# Power_subsystem.net
KiCad netlist of a schematic drawn in Altium Designer
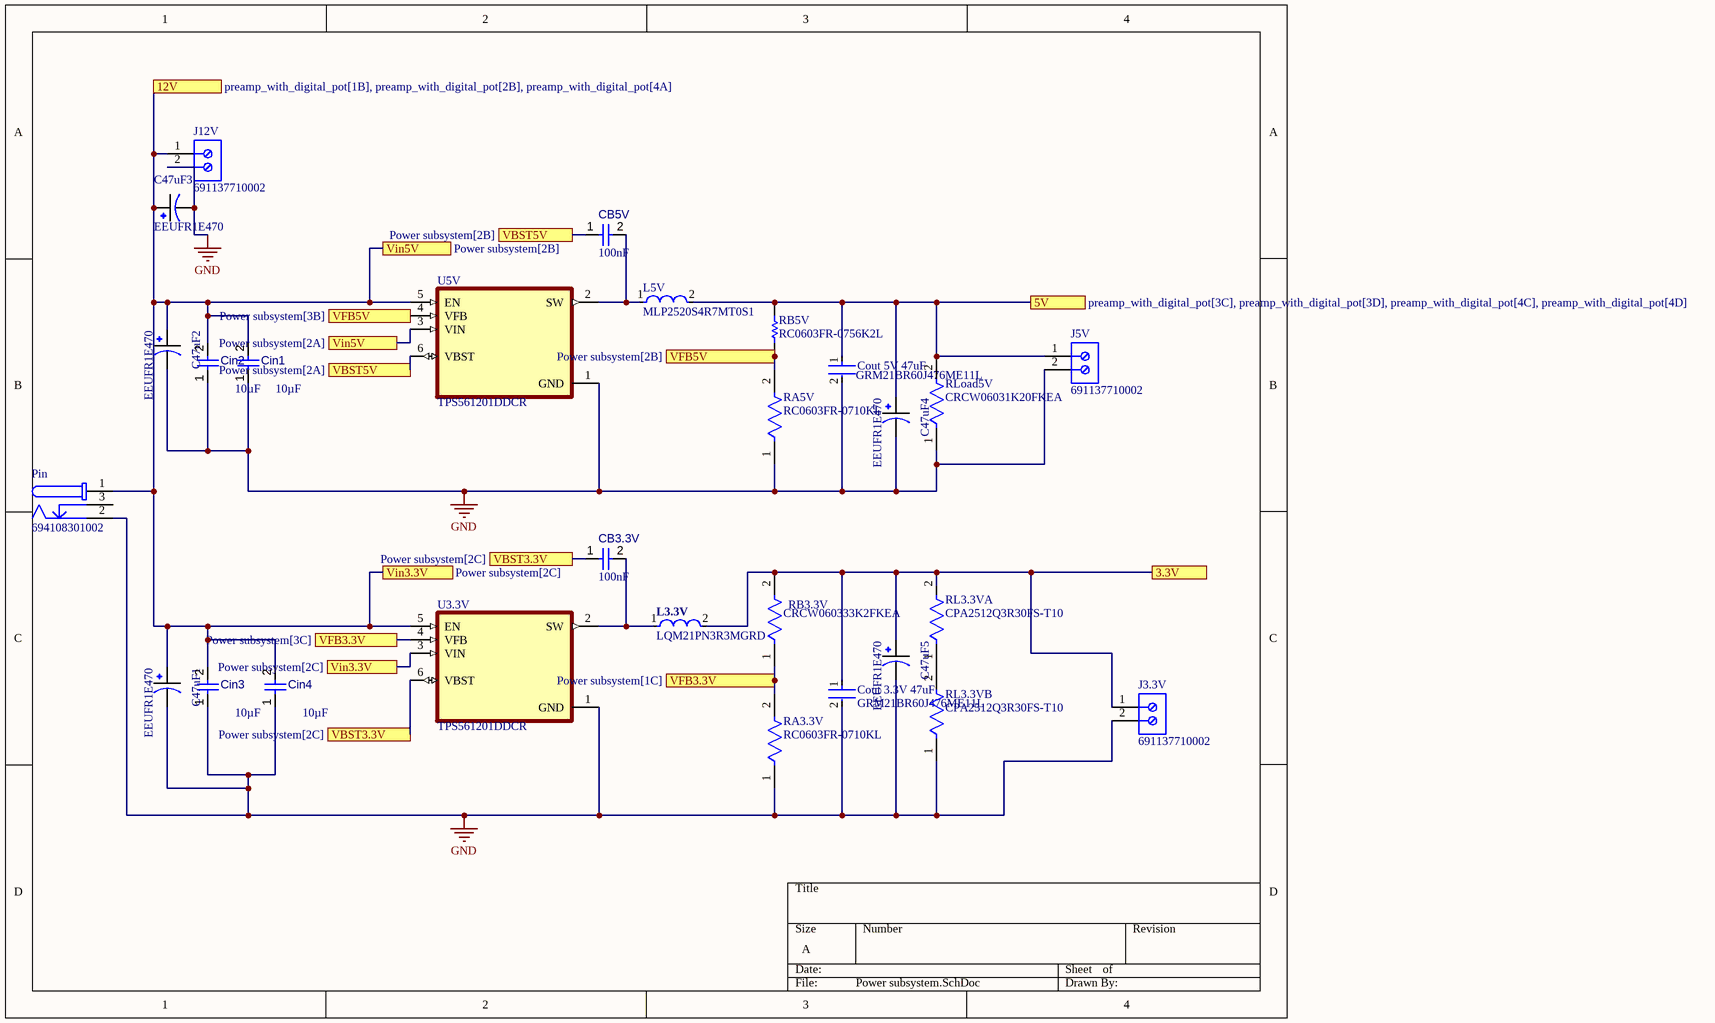
[diagram p0: Power subsystem.SchDoc]

(export (version "E")
  (design (tool "Eeschema 10.0.6"))
  (components
    (comp (ref "C47uF1")
      (value "EEUFR1E470")
      (footprint "*CAPPRD200W50D500H1100_EEUFR1E470(Primary)")
      (libsource (lib "EEUFR1E470") (part "EEUFR1E470"))
    )
    (comp (ref "C47uF2")
      (value "EEUFR1E470")
      (footprint "*CAPPRD200W50D500H1100_EEUFR1E470(Primary)")
      (libsource (lib "EEUFR1E470") (part "EEUFR1E470"))
    )
    (comp (ref "C47uF3")
      (value "EEUFR1E470")
      (footprint "*CAPPRD200W50D500H1100_EEUFR1E470(Primary)")
      (libsource (lib "EEUFR1E470") (part "EEUFR1E470"))
    )
    (comp (ref "C47uF4")
      (value "EEUFR1E470")
      (footprint "*CAPPRD200W50D500H1100_EEUFR1E470(Primary)")
      (libsource (lib "EEUFR1E470") (part "EEUFR1E470"))
    )
    (comp (ref "C47uF5")
      (value "EEUFR1E470")
      (footprint "*CAPPRD200W50D500H1100_EEUFR1E470(Primary)")
      (libsource (lib "EEUFR1E470") (part "EEUFR1E470"))
    )
    (comp (ref "CB3.3V")
      (value "100nF")
      (footprint "CAPC1608X90X40NL10T20")
      (description "Chip Capacitor, 100 nF, +/- 10%, 50 V, 0603 (1608 Metric)")
      (fields (field (name "TOLERANCE") "10%") (field (name "Comment") "Capacitor 100 nF +/-10% 50 V 0603"))
      (libsource (lib "Braeden Murdock") (part "CAP-NP-2"))
    )
    (comp (ref "CB5V")
      (value "100nF")
      (footprint "CAPC1608X90X40NL10T20")
      (description "Chip Capacitor, 100 nF, +/- 10%, 50 V, 0603 (1608 Metric)")
      (fields (field (name "TOLERANCE") "10%") (field (name "Comment") "Capacitor 100 nF +/-10% 50 V 0603"))
      (libsource (lib "Braeden Murdock") (part "CAP-NP-2"))
    )
    (comp (ref "Cin1")
      (value "10µF")
      (footprint "CAPC0805(2012)145_L")
      (description "Chip Capacitor, 10µF +/-20%, 25V, 0805, Thickness 1.45 mm")
      (fields (field (name "TOLERANCE") "10%") (field (name "Comment") "Capacitor 10µF +/-20% 25V 0805"))
      (libsource (lib "Braeden Murdock") (part "CAP-NP-2"))
    )
    (comp (ref "Cin2")
      (value "10µF")
      (footprint "CAPC0805(2012)145_L")
      (description "Chip Capacitor, 10µF +/-20%, 25V, 0805, Thickness 1.45 mm")
      (fields (field (name "TOLERANCE") "10%") (field (name "Comment") "Capacitor 10µF +/-20% 25V 0805"))
      (libsource (lib "Braeden Murdock") (part "CAP-NP-2"))
    )
    (comp (ref "Cin3")
      (value "10µF")
      (footprint "CAPC0805(2012)145_L")
      (description "Chip Capacitor, 10µF +/-20%, 25V, 0805, Thickness 1.45 mm")
      (fields (field (name "TOLERANCE") "10%") (field (name "Comment") "Capacitor 10µF +/-20% 25V 0805"))
      (libsource (lib "Braeden Murdock") (part "CAP-NP-2"))
    )
    (comp (ref "Cin4")
      (value "10µF")
      (footprint "CAPC0805(2012)145_L")
      (description "Chip Capacitor, 10µF +/-20%, 25V, 0805, Thickness 1.45 mm")
      (fields (field (name "TOLERANCE") "10%") (field (name "Comment") "Capacitor 10µF +/-20% 25V 0805"))
      (libsource (lib "Braeden Murdock") (part "CAP-NP-2"))
    )
    (comp (ref "Cout 3.3V 47uF")
      (value "GRM21BR60J476ME11L")
      (footprint "FP-GRM21B-0_2-e0_2_0_7-IPC_B")
      (description "Chip Multilayer Ceramic Capacitors for General Purpose, 0805, 47uF, X5R, 15%, 20%, 6.3V")
      (fields (field (name "TOLERANCE") "20%"))
      (libsource (lib "Altium Content Vault") (part "b4654b650e69147ec39a6b967a45e02"))
    )
    (comp (ref "Cout 5V 47uF")
      (value "GRM21BR60J476ME11L")
      (footprint "FP-GRM21B-0_2-e0_2_0_7-IPC_B")
      (description "Chip Multilayer Ceramic Capacitors for General Purpose, 0805, 47uF, X5R, 15%, 20%, 6.3V")
      (fields (field (name "TOLERANCE") "20%"))
      (libsource (lib "Altium Content Vault") (part "b4654b650e69147ec39a6b967a45e02"))
    )
    (comp (ref "J3.3V")
      (value "691137710002")
      (footprint "691137710002")
      (libsource (lib "Altium Content Vault") (part "TBL - 1R - 02P - Screw"))
    )
    (comp (ref "J5V")
      (value "691137710002")
      (footprint "691137710002")
      (libsource (lib "Altium Content Vault") (part "TBL - 1R - 02P - Screw"))
    )
    (comp (ref "J12V")
      (value "691137710002")
      (footprint "691137710002")
      (libsource (lib "Altium Content Vault") (part "TBL - 1R - 02P - Screw"))
    )
    (comp (ref "L3.3V")
      (value "LQM21PN3R3MGRD")
      (footprint "FP-LQM21PH_G0-MFG")
      (description "Multilayer Type Inductor for Power Lines, 0805 (2012), 3.3μH, 20%, 0.188Ω, 1.0A")
      (fields (field (name "TOLERANCE") "20%"))
      (libsource (lib "Altium Content Vault") (part "725321dda6339637d4d059423bc1c3c"))
    )
    (comp (ref "L5V")
      (value "MLP2520S4R7MT0S1")
      (footprint "FP-MLP2520M-IPC_C")
      (description "Shielded Multilayer Inductor 4.7uH ±20% 1000mA 169mΩ SMD 1008")
      (fields (field (name "TOLERANCE") "20%"))
      (libsource (lib "Altium Content Vault") (part "725321dda6339637d4d059423bc1c3c"))
    )
    (comp (ref "Pin")
      (value "694108301002")
      (footprint "694108301002")
      (libsource (lib "Altium Content Vault") (part "DC Power Jack"))
    )
    (comp (ref "RA3.3V")
      (value "RC0603FR-0710KL")
      (footprint "FP-RC0603-0_55-IPC_C")
      (description "RES 10K OHM 1% 1/10W 0603")
      (fields (field (name "TOLERANCE") "1%"))
      (libsource (lib "Altium Content Vault") (part "1029c3af85768c4190bb7ad29bc67b5"))
    )
    (comp (ref "RA5V")
      (value "RC0603FR-0710KL")
      (footprint "FP-RC0603-0_55-IPC_C")
      (description "RES 10K OHM 1% 1/10W 0603")
      (fields (field (name "TOLERANCE") "1%"))
      (libsource (lib "Altium Content Vault") (part "1029c3af85768c4190bb7ad29bc67b5"))
    )
    (comp (ref "RB3.3V")
      (value "CRCW060333K2FKEA")
      (footprint "FP-CRCW0603-e3-IPC_B")
      (description "RES Thick Film, 33.2kΩ, 1%, 0.1W, 100ppm/°C, 0603")
      (fields (field (name "TOLERANCE") "1%"))
      (libsource (lib "Altium Content Vault") (part "1029c3af85768c4190bb7ad29bc67b5"))
    )
    (comp (ref "RB5V")
      (value "RC0603FR-0756K2L")
      (footprint "RESC1608X55X25LL10T15")
      (description "Chip Resistor, 56.2 KOhm, +/- 1%, 0.1 W, -55 to 155 degC, 0603 (1608 Metric), RoHS, Tape and Reel")
      (libsource (lib "Altium Content Vault") (part "RES-2"))
    )
    (comp (ref "RL3.3VA")
      (value "CPA2512Q3R30FS-T10")
      (footprint "FP-CPA2512-MFG")
      (description "CPA2512Q3R30FS-T10 CPA Series 2512 16 W 3.3O ±1% ±50 ppm/°C SMT Thin Film Chip Power Resistor")
      (fields (field (name "TOLERANCE") "1%"))
      (libsource (lib "Altium Content Vault") (part "1029c3af85768c4190bb7ad29bc67b5"))
    )
    (comp (ref "RL3.3VB")
      (value "CPA2512Q3R30FS-T10")
      (footprint "FP-CPA2512-MFG")
      (description "CPA2512Q3R30FS-T10 CPA Series 2512 16 W 3.3O ±1% ±50 ppm/°C SMT Thin Film Chip Power Resistor")
      (fields (field (name "TOLERANCE") "1%"))
      (libsource (lib "Altium Content Vault") (part "1029c3af85768c4190bb7ad29bc67b5"))
    )
    (comp (ref "RLoad5V")
      (value "CRCW06031K20FKEA")
      (footprint "FP-CRCW0603-e3-MFG")
      (description "RES Thick Film, 1.2kΩ, 1%, 0.1W, 100ppm/°C, 0603")
      (fields (field (name "TOLERANCE") "1%"))
      (libsource (lib "Altium Content Vault") (part "1029c3af85768c4190bb7ad29bc67b5"))
    )
    (comp (ref "U3.3V")
      (value "TPS561201DDCR")
      (footprint "SOT95P280X110-6N")
      (description "4.5V to 17V Input, 1A Synchronous Step-Down Voltage Regulator in 6-pin SOT-23")
      (fields (field (name "MF") "Texas Instruments"))
      (libsource (lib "Braeden Murdock") (part "TPS561201DDCR"))
    )
    (comp (ref "U5V")
      (value "TPS561201DDCR")
      (footprint "SOT95P280X110-6N")
      (description "4.5V to 17V Input, 1A Synchronous Step-Down Voltage Regulator in 6-pin SOT-23")
      (fields (field (name "MF") "Texas Instruments"))
      (libsource (lib "Braeden Murdock") (part "TPS561201DDCR"))
    )
  )
  (nets
    (net (code "1") (name "/3.3V") (class "Default")
      (node (ref "C47uF5") (pin "P") (pinfunction "P_P") (pintype "passive"))
      (node (ref "Cout 3.3V 47uF") (pin "1") (pinfunction "1_1") (pintype "passive"))
      (node (ref "J3.3V") (pin "1") (pinfunction "1_1") (pintype "passive"))
      (node (ref "L3.3V") (pin "2") (pinfunction "2_2") (pintype "passive"))
      (node (ref "RB3.3V") (pin "2") (pinfunction "2_2") (pintype "passive"))
      (node (ref "RL3.3VA") (pin "2") (pinfunction "2_2") (pintype "passive"))
    )
    (net (code "2") (name "/5V") (class "Default")
      (node (ref "C47uF4") (pin "P") (pinfunction "P_P") (pintype "passive"))
      (node (ref "Cout 5V 47uF") (pin "1") (pinfunction "1_1") (pintype "passive"))
      (node (ref "J5V") (pin "1") (pinfunction "1_1") (pintype "passive"))
      (node (ref "L5V") (pin "2") (pinfunction "2_2") (pintype "passive"))
      (node (ref "RB5V") (pin "2") (pinfunction "2_2") (pintype "passive"))
      (node (ref "RLoad5V") (pin "2") (pinfunction "2_2") (pintype "passive"))
    )
    (net (code "3") (name "/12V") (class "Default")
      (node (ref "C47uF1") (pin "P") (pinfunction "P_P") (pintype "passive"))
      (node (ref "C47uF2") (pin "P") (pinfunction "P_P") (pintype "passive"))
      (node (ref "C47uF3") (pin "P") (pinfunction "P_P") (pintype "passive"))
      (node (ref "Cin1") (pin "2") (pinfunction "2_2") (pintype "passive"))
      (node (ref "Cin2") (pin "2") (pinfunction "2_2") (pintype "passive"))
      (node (ref "Cin3") (pin "2") (pinfunction "2_2") (pintype "passive"))
      (node (ref "Cin4") (pin "2") (pinfunction "2_2") (pintype "passive"))
      (node (ref "J12V") (pin "1") (pinfunction "1_1") (pintype "passive"))
      (node (ref "Pin") (pin "1") (pinfunction "1_1") (pintype "passive"))
      (node (ref "U3.3V") (pin "3") (pinfunction "VIN_3") (pintype "input"))
      (node (ref "U3.3V") (pin "5") (pinfunction "EN_5") (pintype "input"))
      (node (ref "U5V") (pin "3") (pinfunction "VIN_3") (pintype "input"))
      (node (ref "U5V") (pin "5") (pinfunction "EN_5") (pintype "input"))
    )
    (net (code "4") (name "/VBST3.3V") (class "Default")
      (node (ref "CB3.3V") (pin "1") (pinfunction "1_1") (pintype "passive"))
      (node (ref "U3.3V") (pin "6") (pinfunction "VBST_6") (pintype "bidirectional"))
    )
    (net (code "5") (name "/VBST5V") (class "Default")
      (node (ref "CB5V") (pin "1") (pinfunction "1_1") (pintype "passive"))
      (node (ref "U5V") (pin "6") (pinfunction "VBST_6") (pintype "bidirectional"))
    )
    (net (code "6") (name "/VFB3.3V") (class "Default")
      (node (ref "RA3.3V") (pin "2") (pinfunction "2_2") (pintype "passive"))
      (node (ref "RB3.3V") (pin "1") (pinfunction "1_1") (pintype "passive"))
      (node (ref "U3.3V") (pin "4") (pinfunction "VFB_4") (pintype "input"))
    )
    (net (code "7") (name "/VFB5V") (class "Default")
      (node (ref "RA5V") (pin "2") (pinfunction "2_2") (pintype "passive"))
      (node (ref "RB5V") (pin "1") (pinfunction "1_1") (pintype "passive"))
      (node (ref "U5V") (pin "4") (pinfunction "VFB_4") (pintype "input"))
    )
    (net (code "8") (name "GND") (class "Default")
      (node (ref "C47uF1") (pin "N") (pinfunction "N_N") (pintype "passive"))
      (node (ref "C47uF2") (pin "N") (pinfunction "N_N") (pintype "passive"))
      (node (ref "C47uF3") (pin "N") (pinfunction "N_N") (pintype "passive"))
      (node (ref "C47uF4") (pin "N") (pinfunction "N_N") (pintype "passive"))
      (node (ref "C47uF5") (pin "N") (pinfunction "N_N") (pintype "passive"))
      (node (ref "Cin1") (pin "1") (pinfunction "1_1") (pintype "passive"))
      (node (ref "Cin2") (pin "1") (pinfunction "1_1") (pintype "passive"))
      (node (ref "Cin3") (pin "1") (pinfunction "1_1") (pintype "passive"))
      (node (ref "Cin4") (pin "1") (pinfunction "1_1") (pintype "passive"))
      (node (ref "Cout 3.3V 47uF") (pin "2") (pinfunction "2_2") (pintype "passive"))
      (node (ref "Cout 5V 47uF") (pin "2") (pinfunction "2_2") (pintype "passive"))
      (node (ref "J12V") (pin "2") (pinfunction "2_2") (pintype "passive"))
      (node (ref "J3.3V") (pin "2") (pinfunction "2_2") (pintype "passive"))
      (node (ref "J5V") (pin "2") (pinfunction "2_2") (pintype "passive"))
      (node (ref "Pin") (pin "2") (pinfunction "2_2") (pintype "passive"))
      (node (ref "RA3.3V") (pin "1") (pinfunction "1_1") (pintype "passive"))
      (node (ref "RA5V") (pin "1") (pinfunction "1_1") (pintype "passive"))
      (node (ref "RL3.3VB") (pin "1") (pinfunction "1_1") (pintype "passive"))
      (node (ref "RLoad5V") (pin "1") (pinfunction "1_1") (pintype "passive"))
      (node (ref "U3.3V") (pin "1") (pinfunction "GND_1") (pintype "power_in"))
      (node (ref "U5V") (pin "1") (pinfunction "GND_1") (pintype "power_in"))
    )
    (net (code "9") (name "Net-(RL3.3VA-Pad1)") (class "Default")
      (node (ref "RL3.3VA") (pin "1") (pinfunction "1_1") (pintype "passive"))
      (node (ref "RL3.3VB") (pin "2") (pinfunction "2_2") (pintype "passive"))
    )
    (net (code "10") (name "Net-(U3.3V-SW)") (class "Default")
      (node (ref "CB3.3V") (pin "2") (pinfunction "2_2") (pintype "passive"))
      (node (ref "L3.3V") (pin "1") (pinfunction "1_1") (pintype "passive"))
      (node (ref "U3.3V") (pin "2") (pinfunction "SW_2") (pintype "output"))
    )
    (net (code "11") (name "Net-(U5V-SW)") (class "Default")
      (node (ref "CB5V") (pin "2") (pinfunction "2_2") (pintype "passive"))
      (node (ref "L5V") (pin "1") (pinfunction "1_1") (pintype "passive"))
      (node (ref "U5V") (pin "2") (pinfunction "SW_2") (pintype "output"))
    )
    (net (code "12") (name "unconnected-(Pin-Pad3)") (class "Default")
      (node (ref "Pin") (pin "3") (pinfunction "3_3") (pintype "passive"))
    )
  )
)
